# small.net
KiCad netlist of a schematic drawn in EAGLE
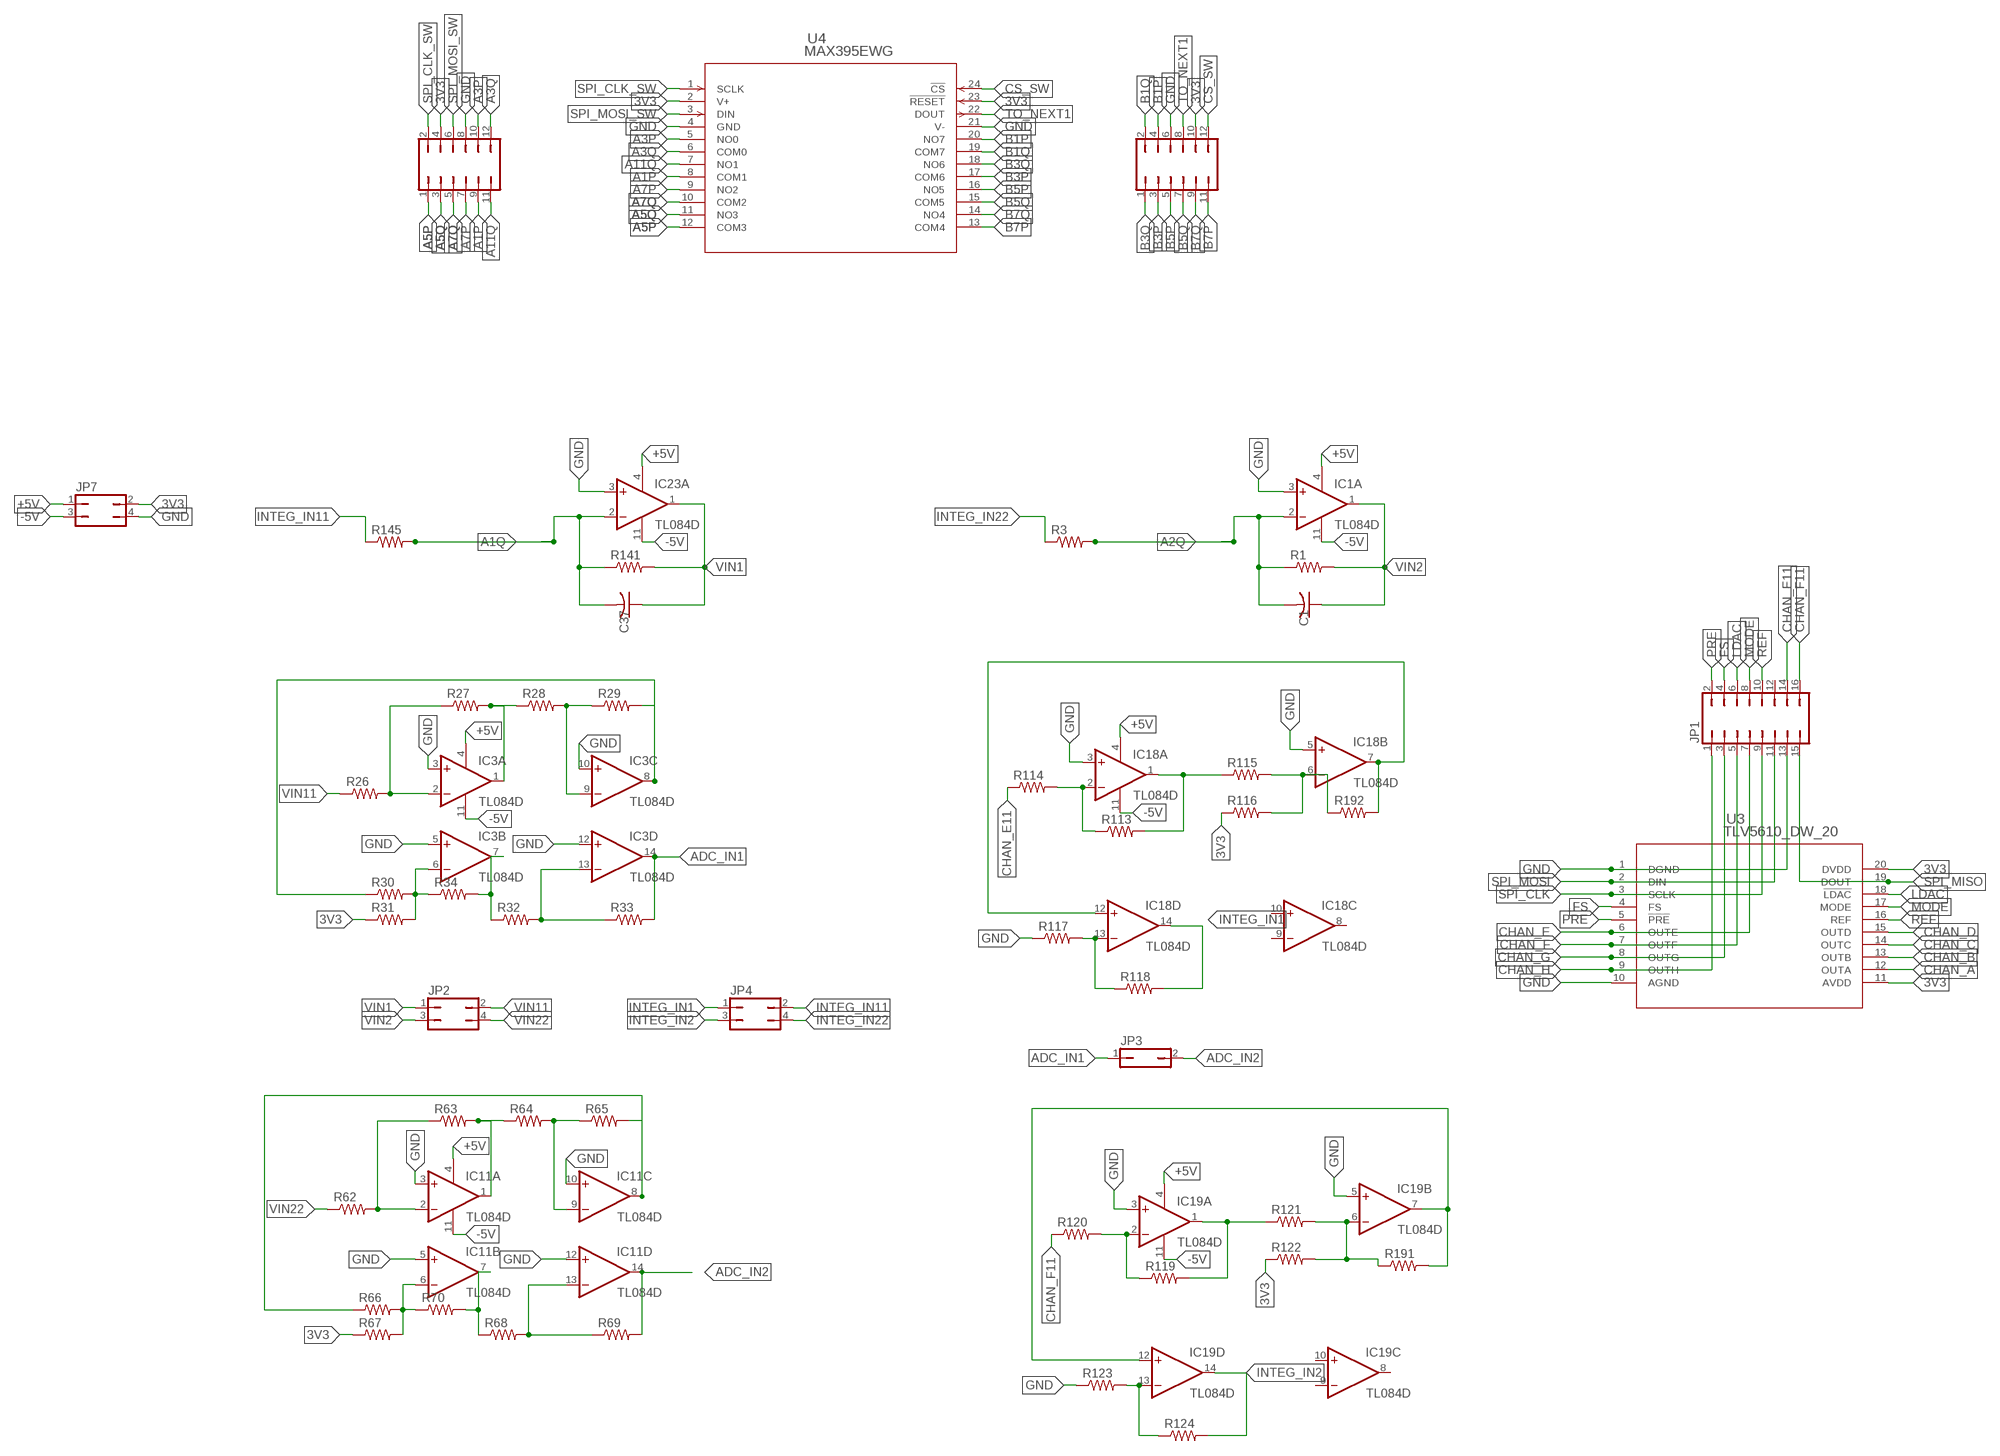
[diagram p0: schematic, sheet 1]

(export (version "E")
  (design (tool "Eeschema 10.0.6"))
  (components
    (comp (ref "C1")
      (value "C-USC1206")
      (footprint "eagle-import:C1206")
      (libsource (lib "eagle-import") (part "C-USC1206"))
    )
    (comp (ref "C37")
      (value "C-USC1206")
      (footprint "eagle-import:C1206")
      (libsource (lib "eagle-import") (part "C-USC1206"))
    )
    (comp (ref "IC1")
      (value "TL084D")
      (footprint "eagle-import:SO14")
      (libsource (lib "eagle-import") (part "TL084D"))
    )
    (comp (ref "IC3")
      (value "TL084D")
      (footprint "eagle-import:SO14")
      (libsource (lib "eagle-import") (part "TL084D"))
    )
    (comp (ref "IC11")
      (value "TL084D")
      (footprint "eagle-import:SO14")
      (libsource (lib "eagle-import") (part "TL084D"))
    )
    (comp (ref "IC18")
      (value "TL084D")
      (footprint "eagle-import:SO14")
      (libsource (lib "eagle-import") (part "TL084D"))
    )
    (comp (ref "IC19")
      (value "TL084D")
      (footprint "eagle-import:SO14")
      (libsource (lib "eagle-import") (part "TL084D"))
    )
    (comp (ref "IC23")
      (value "TL084D")
      (footprint "eagle-import:SO14")
      (libsource (lib "eagle-import") (part "TL084D"))
    )
    (comp (ref "JP1")
      (value "JP8Q")
      (footprint "eagle-import:JP8Q")
      (libsource (lib "eagle-import") (part "JP8Q"))
    )
    (comp (ref "JP2")
      (value "JP2Q")
      (footprint "eagle-import:JP2Q")
      (libsource (lib "eagle-import") (part "JP2Q"))
    )
    (comp (ref "JP3")
      (value "JP1Q")
      (footprint "eagle-import:JP1")
      (libsource (lib "eagle-import") (part "JP1Q"))
    )
    (comp (ref "JP4")
      (value "JP2Q")
      (footprint "eagle-import:JP2Q")
      (libsource (lib "eagle-import") (part "JP2Q"))
    )
    (comp (ref "JP5")
      (value "JP6Q")
      (footprint "eagle-import:JP6Q")
      (libsource (lib "eagle-import") (part "JP6Q"))
    )
    (comp (ref "JP6")
      (value "JP6Q")
      (footprint "eagle-import:JP6Q")
      (libsource (lib "eagle-import") (part "JP6Q"))
    )
    (comp (ref "JP7")
      (value "JP2Q")
      (footprint "eagle-import:JP2Q")
      (libsource (lib "eagle-import") (part "JP2Q"))
    )
    (comp (ref "R1")
      (value "R-US_R1206")
      (footprint "eagle-import:R1206")
      (libsource (lib "eagle-import") (part "R-US_R1206"))
    )
    (comp (ref "R3")
      (value "R-US_R1206")
      (footprint "eagle-import:R1206")
      (libsource (lib "eagle-import") (part "R-US_R1206"))
    )
    (comp (ref "R26")
      (value "R-US_R1206")
      (footprint "eagle-import:R1206")
      (libsource (lib "eagle-import") (part "R-US_R1206"))
    )
    (comp (ref "R27")
      (value "R-US_R1206")
      (footprint "eagle-import:R1206")
      (libsource (lib "eagle-import") (part "R-US_R1206"))
    )
    (comp (ref "R28")
      (value "R-US_R1206")
      (footprint "eagle-import:R1206")
      (libsource (lib "eagle-import") (part "R-US_R1206"))
    )
    (comp (ref "R29")
      (value "R-US_R1206")
      (footprint "eagle-import:R1206")
      (libsource (lib "eagle-import") (part "R-US_R1206"))
    )
    (comp (ref "R30")
      (value "R-US_R1206")
      (footprint "eagle-import:R1206")
      (libsource (lib "eagle-import") (part "R-US_R1206"))
    )
    (comp (ref "R31")
      (value "R-US_R1206")
      (footprint "eagle-import:R1206")
      (libsource (lib "eagle-import") (part "R-US_R1206"))
    )
    (comp (ref "R32")
      (value "R-US_R1206")
      (footprint "eagle-import:R1206")
      (libsource (lib "eagle-import") (part "R-US_R1206"))
    )
    (comp (ref "R33")
      (value "R-US_R1206")
      (footprint "eagle-import:R1206")
      (libsource (lib "eagle-import") (part "R-US_R1206"))
    )
    (comp (ref "R34")
      (value "R-US_R1206")
      (footprint "eagle-import:R1206")
      (libsource (lib "eagle-import") (part "R-US_R1206"))
    )
    (comp (ref "R62")
      (value "R-US_R1206")
      (footprint "eagle-import:R1206")
      (libsource (lib "eagle-import") (part "R-US_R1206"))
    )
    (comp (ref "R63")
      (value "R-US_R1206")
      (footprint "eagle-import:R1206")
      (libsource (lib "eagle-import") (part "R-US_R1206"))
    )
    (comp (ref "R64")
      (value "R-US_R1206")
      (footprint "eagle-import:R1206")
      (libsource (lib "eagle-import") (part "R-US_R1206"))
    )
    (comp (ref "R65")
      (value "R-US_R1206")
      (footprint "eagle-import:R1206")
      (libsource (lib "eagle-import") (part "R-US_R1206"))
    )
    (comp (ref "R66")
      (value "R-US_R1206")
      (footprint "eagle-import:R1206")
      (libsource (lib "eagle-import") (part "R-US_R1206"))
    )
    (comp (ref "R67")
      (value "R-US_R1206")
      (footprint "eagle-import:R1206")
      (libsource (lib "eagle-import") (part "R-US_R1206"))
    )
    (comp (ref "R68")
      (value "R-US_R1206")
      (footprint "eagle-import:R1206")
      (libsource (lib "eagle-import") (part "R-US_R1206"))
    )
    (comp (ref "R69")
      (value "R-US_R1206")
      (footprint "eagle-import:R1206")
      (libsource (lib "eagle-import") (part "R-US_R1206"))
    )
    (comp (ref "R70")
      (value "R-US_R1206")
      (footprint "eagle-import:R1206")
      (libsource (lib "eagle-import") (part "R-US_R1206"))
    )
    (comp (ref "R113")
      (value "R-US_R1206")
      (footprint "eagle-import:R1206")
      (libsource (lib "eagle-import") (part "R-US_R1206"))
    )
    (comp (ref "R114")
      (value "R-US_R1206")
      (footprint "eagle-import:R1206")
      (libsource (lib "eagle-import") (part "R-US_R1206"))
    )
    (comp (ref "R115")
      (value "R-US_R1206")
      (footprint "eagle-import:R1206")
      (libsource (lib "eagle-import") (part "R-US_R1206"))
    )
    (comp (ref "R116")
      (value "R-US_R1206")
      (footprint "eagle-import:R1206")
      (libsource (lib "eagle-import") (part "R-US_R1206"))
    )
    (comp (ref "R117")
      (value "R-US_R1206")
      (footprint "eagle-import:R1206")
      (libsource (lib "eagle-import") (part "R-US_R1206"))
    )
    (comp (ref "R118")
      (value "R-US_R1206")
      (footprint "eagle-import:R1206")
      (libsource (lib "eagle-import") (part "R-US_R1206"))
    )
    (comp (ref "R119")
      (value "R-US_R1206")
      (footprint "eagle-import:R1206")
      (libsource (lib "eagle-import") (part "R-US_R1206"))
    )
    (comp (ref "R120")
      (value "R-US_R1206")
      (footprint "eagle-import:R1206")
      (libsource (lib "eagle-import") (part "R-US_R1206"))
    )
    (comp (ref "R121")
      (value "R-US_R1206")
      (footprint "eagle-import:R1206")
      (libsource (lib "eagle-import") (part "R-US_R1206"))
    )
    (comp (ref "R122")
      (value "R-US_R1206")
      (footprint "eagle-import:R1206")
      (libsource (lib "eagle-import") (part "R-US_R1206"))
    )
    (comp (ref "R123")
      (value "R-US_R1206")
      (footprint "eagle-import:R1206")
      (libsource (lib "eagle-import") (part "R-US_R1206"))
    )
    (comp (ref "R124")
      (value "R-US_R1206")
      (footprint "eagle-import:R1206")
      (libsource (lib "eagle-import") (part "R-US_R1206"))
    )
    (comp (ref "R141")
      (value "R-US_R1206")
      (footprint "eagle-import:R1206")
      (libsource (lib "eagle-import") (part "R-US_R1206"))
    )
    (comp (ref "R145")
      (value "R-US_R1206")
      (footprint "eagle-import:R1206")
      (libsource (lib "eagle-import") (part "R-US_R1206"))
    )
    (comp (ref "R191")
      (value "R-US_R1206")
      (footprint "eagle-import:R1206")
      (libsource (lib "eagle-import") (part "R-US_R1206"))
    )
    (comp (ref "R192")
      (value "R-US_R1206")
      (footprint "eagle-import:R1206")
      (libsource (lib "eagle-import") (part "R-US_R1206"))
    )
    (comp (ref "U3")
      (value "TLV5610_DW_20")
      (footprint "eagle-import:DW20")
      (libsource (lib "eagle-import") (part "TLV5610_DW_20"))
    )
    (comp (ref "U4")
      (value "MAX395EWG")
      (footprint "eagle-import:21-0042B_24")
      (fields (field (name "MANUFACTURER_PART_NUMBER") "max395ewg"))
      (libsource (lib "eagle-import") (part "MAX395EWG"))
    )
  )
  (nets
    (net (code "1") (name "+5V") (class "Default")
      (node (ref "IC1") (pin "4") (pinfunction "V+_4") (pintype "power_in"))
      (node (ref "IC11") (pin "4") (pinfunction "V+_4") (pintype "power_in"))
      (node (ref "IC18") (pin "4") (pinfunction "V+_4") (pintype "power_in"))
      (node (ref "IC19") (pin "4") (pinfunction "V+_4") (pintype "power_in"))
      (node (ref "IC23") (pin "4") (pinfunction "V+_4") (pintype "power_in"))
      (node (ref "IC3") (pin "4") (pinfunction "V+_4") (pintype "power_in"))
      (node (ref "JP7") (pin "1") (pinfunction "1_1") (pintype "passive"))
    )
    (net (code "2") (name "-5V") (class "Default")
      (node (ref "IC1") (pin "11") (pinfunction "V-_11") (pintype "power_in"))
      (node (ref "IC11") (pin "11") (pinfunction "V-_11") (pintype "power_in"))
      (node (ref "IC18") (pin "11") (pinfunction "V-_11") (pintype "power_in"))
      (node (ref "IC19") (pin "11") (pinfunction "V-_11") (pintype "power_in"))
      (node (ref "IC23") (pin "11") (pinfunction "V-_11") (pintype "power_in"))
      (node (ref "IC3") (pin "11") (pinfunction "V-_11") (pintype "power_in"))
      (node (ref "JP7") (pin "3") (pinfunction "3_3") (pintype "passive"))
    )
    (net (code "3") (name "3V3") (class "Default")
      (node (ref "JP5") (pin "4") (pinfunction "4_4") (pintype "passive"))
      (node (ref "JP6") (pin "10") (pinfunction "10_10") (pintype "passive"))
      (node (ref "JP7") (pin "2") (pinfunction "2_2") (pintype "passive"))
      (node (ref "R116") (pin "1") (pinfunction "1_1") (pintype "passive"))
      (node (ref "R122") (pin "1") (pinfunction "1_1") (pintype "passive"))
      (node (ref "R31") (pin "1") (pinfunction "1_1") (pintype "passive"))
      (node (ref "R67") (pin "1") (pinfunction "1_1") (pintype "passive"))
      (node (ref "U3") (pin "11") (pinfunction "AVDD_11") (pintype "power_in"))
      (node (ref "U3") (pin "20") (pinfunction "DVDD_20") (pintype "power_in"))
      (node (ref "U4") (pin "2") (pinfunction "V+_2") (pintype "power_in"))
      (node (ref "U4") (pin "23") (pinfunction "~{RESET}_23") (pintype "input"))
    )
    (net (code "4") (name "A1P") (class "Default")
      (node (ref "JP5") (pin "9") (pinfunction "9_9") (pintype "passive"))
      (node (ref "U4") (pin "8") (pinfunction "COM1_8") (pintype "passive"))
    )
    (net (code "5") (name "A1Q") (class "Default")
      (node (ref "C37") (pin "2") (pinfunction "2_2") (pintype "passive"))
      (node (ref "IC23") (pin "2") (pinfunction "-IN_2") (pintype "input"))
      (node (ref "R141") (pin "1") (pinfunction "1_1") (pintype "passive"))
      (node (ref "R145") (pin "2") (pinfunction "2_2") (pintype "passive"))
    )
    (net (code "6") (name "A2Q") (class "Default")
      (node (ref "C1") (pin "2") (pinfunction "2_2") (pintype "passive"))
      (node (ref "IC1") (pin "2") (pinfunction "-IN_2") (pintype "input"))
      (node (ref "R1") (pin "1") (pinfunction "1_1") (pintype "passive"))
      (node (ref "R3") (pin "2") (pinfunction "2_2") (pintype "passive"))
    )
    (net (code "7") (name "A3P") (class "Default")
      (node (ref "JP5") (pin "10") (pinfunction "10_10") (pintype "passive"))
      (node (ref "U4") (pin "5") (pinfunction "NO0_5") (pintype "passive"))
    )
    (net (code "8") (name "A3Q") (class "Default")
      (node (ref "JP5") (pin "12") (pinfunction "12_12") (pintype "passive"))
      (node (ref "U4") (pin "6") (pinfunction "COM0_6") (pintype "passive"))
    )
    (net (code "9") (name "A5P") (class "Default")
      (node (ref "JP5") (pin "1") (pinfunction "1_1") (pintype "passive"))
      (node (ref "U4") (pin "12") (pinfunction "COM3_12") (pintype "passive"))
    )
    (net (code "10") (name "A5Q") (class "Default")
      (node (ref "JP5") (pin "3") (pinfunction "3_3") (pintype "passive"))
      (node (ref "U4") (pin "11") (pinfunction "NO3_11") (pintype "passive"))
    )
    (net (code "11") (name "A7P") (class "Default")
      (node (ref "JP5") (pin "7") (pinfunction "7_7") (pintype "passive"))
      (node (ref "U4") (pin "9") (pinfunction "NO2_9") (pintype "passive"))
    )
    (net (code "12") (name "A7Q") (class "Default")
      (node (ref "JP5") (pin "5") (pinfunction "5_5") (pintype "passive"))
      (node (ref "U4") (pin "10") (pinfunction "COM2_10") (pintype "passive"))
    )
    (net (code "13") (name "A11Q") (class "Default")
      (node (ref "JP5") (pin "11") (pinfunction "11_11") (pintype "passive"))
      (node (ref "U4") (pin "7") (pinfunction "NO1_7") (pintype "passive"))
    )
    (net (code "14") (name "ADC_IN1") (class "Default")
      (node (ref "IC3") (pin "14") (pinfunction "OUT_14") (pintype "output"))
      (node (ref "JP3") (pin "1") (pinfunction "1_1") (pintype "passive"))
      (node (ref "R33") (pin "2") (pinfunction "2_2") (pintype "passive"))
    )
    (net (code "15") (name "ADC_IN2") (class "Default")
      (node (ref "IC11") (pin "14") (pinfunction "OUT_14") (pintype "output"))
      (node (ref "JP3") (pin "2") (pinfunction "2_2") (pintype "passive"))
      (node (ref "R69") (pin "2") (pinfunction "2_2") (pintype "passive"))
    )
    (net (code "16") (name "B1P") (class "Default")
      (node (ref "JP6") (pin "4") (pinfunction "4_4") (pintype "passive"))
      (node (ref "U4") (pin "20") (pinfunction "NO7_20") (pintype "passive"))
    )
    (net (code "17") (name "B1Q") (class "Default")
      (node (ref "JP6") (pin "2") (pinfunction "2_2") (pintype "passive"))
      (node (ref "U4") (pin "19") (pinfunction "COM7_19") (pintype "passive"))
    )
    (net (code "18") (name "B3P") (class "Default")
      (node (ref "JP6") (pin "3") (pinfunction "3_3") (pintype "passive"))
      (node (ref "U4") (pin "17") (pinfunction "COM6_17") (pintype "passive"))
    )
    (net (code "19") (name "B3Q") (class "Default")
      (node (ref "JP6") (pin "1") (pinfunction "1_1") (pintype "passive"))
      (node (ref "U4") (pin "18") (pinfunction "NO6_18") (pintype "passive"))
    )
    (net (code "20") (name "B5P") (class "Default")
      (node (ref "JP6") (pin "5") (pinfunction "5_5") (pintype "passive"))
      (node (ref "U4") (pin "16") (pinfunction "NO5_16") (pintype "passive"))
    )
    (net (code "21") (name "B5Q") (class "Default")
      (node (ref "JP6") (pin "7") (pinfunction "7_7") (pintype "passive"))
      (node (ref "U4") (pin "15") (pinfunction "COM5_15") (pintype "passive"))
    )
    (net (code "22") (name "B7P") (class "Default")
      (node (ref "JP6") (pin "11") (pinfunction "11_11") (pintype "passive"))
      (node (ref "U4") (pin "13") (pinfunction "COM4_13") (pintype "passive"))
    )
    (net (code "23") (name "B7Q") (class "Default")
      (node (ref "JP6") (pin "9") (pinfunction "9_9") (pintype "passive"))
      (node (ref "U4") (pin "14") (pinfunction "NO4_14") (pintype "passive"))
    )
    (net (code "24") (name "CHAN_A") (class "Default")
      (node (ref "U3") (pin "12") (pinfunction "OUTA_12") (pintype "output"))
    )
    (net (code "25") (name "CHAN_B") (class "Default")
      (node (ref "U3") (pin "13") (pinfunction "OUTB_13") (pintype "output"))
    )
    (net (code "26") (name "CHAN_C") (class "Default")
      (node (ref "U3") (pin "14") (pinfunction "OUTC_14") (pintype "output"))
    )
    (net (code "27") (name "CHAN_D") (class "Default")
      (node (ref "U3") (pin "15") (pinfunction "OUTD_15") (pintype "output"))
    )
    (net (code "28") (name "CHAN_E") (class "Default")
      (node (ref "JP1") (pin "7") (pinfunction "7_7") (pintype "passive"))
      (node (ref "U3") (pin "6") (pinfunction "OUTE_6") (pintype "output"))
    )
    (net (code "29") (name "CHAN_E11") (class "Default")
      (node (ref "JP1") (pin "14") (pinfunction "14_14") (pintype "passive"))
      (node (ref "R114") (pin "1") (pinfunction "1_1") (pintype "passive"))
    )
    (net (code "30") (name "CHAN_F") (class "Default")
      (node (ref "JP1") (pin "5") (pinfunction "5_5") (pintype "passive"))
      (node (ref "U3") (pin "7") (pinfunction "OUTF_7") (pintype "output"))
    )
    (net (code "31") (name "CHAN_F11") (class "Default")
      (node (ref "JP1") (pin "16") (pinfunction "16_16") (pintype "passive"))
      (node (ref "R120") (pin "1") (pinfunction "1_1") (pintype "passive"))
    )
    (net (code "32") (name "CHAN_G") (class "Default")
      (node (ref "JP1") (pin "3") (pinfunction "3_3") (pintype "passive"))
      (node (ref "U3") (pin "8") (pinfunction "OUTG_8") (pintype "output"))
    )
    (net (code "33") (name "CHAN_H") (class "Default")
      (node (ref "JP1") (pin "1") (pinfunction "1_1") (pintype "passive"))
      (node (ref "U3") (pin "9") (pinfunction "OUTH_9") (pintype "output"))
    )
    (net (code "34") (name "CS_SW") (class "Default")
      (node (ref "JP6") (pin "12") (pinfunction "12_12") (pintype "passive"))
      (node (ref "U4") (pin "24") (pinfunction "~{CS}_24") (pintype "input"))
    )
    (net (code "35") (name "FS") (class "Default")
      (node (ref "JP1") (pin "4") (pinfunction "4_4") (pintype "passive"))
      (node (ref "U3") (pin "4") (pinfunction "FS_4") (pintype "input"))
    )
    (net (code "36") (name "GND") (class "Default")
      (node (ref "IC1") (pin "3") (pinfunction "+IN_3") (pintype "input"))
      (node (ref "IC11") (pin "10") (pinfunction "+IN_10") (pintype "input"))
      (node (ref "IC11") (pin "12") (pinfunction "+IN_12") (pintype "input"))
      (node (ref "IC11") (pin "3") (pinfunction "+IN_3") (pintype "input"))
      (node (ref "IC11") (pin "5") (pinfunction "+IN_5") (pintype "input"))
      (node (ref "IC18") (pin "3") (pinfunction "+IN_3") (pintype "input"))
      (node (ref "IC18") (pin "5") (pinfunction "+IN_5") (pintype "input"))
      (node (ref "IC19") (pin "3") (pinfunction "+IN_3") (pintype "input"))
      (node (ref "IC19") (pin "5") (pinfunction "+IN_5") (pintype "input"))
      (node (ref "IC23") (pin "3") (pinfunction "+IN_3") (pintype "input"))
      (node (ref "IC3") (pin "10") (pinfunction "+IN_10") (pintype "input"))
      (node (ref "IC3") (pin "12") (pinfunction "+IN_12") (pintype "input"))
      (node (ref "IC3") (pin "3") (pinfunction "+IN_3") (pintype "input"))
      (node (ref "IC3") (pin "5") (pinfunction "+IN_5") (pintype "input"))
      (node (ref "JP1") (pin "13") (pinfunction "13_13") (pintype "passive"))
      (node (ref "JP5") (pin "8") (pinfunction "8_8") (pintype "passive"))
      (node (ref "JP6") (pin "6") (pinfunction "6_6") (pintype "passive"))
      (node (ref "JP7") (pin "4") (pinfunction "4_4") (pintype "passive"))
      (node (ref "R117") (pin "1") (pinfunction "1_1") (pintype "passive"))
      (node (ref "R123") (pin "1") (pinfunction "1_1") (pintype "passive"))
      (node (ref "U3") (pin "1") (pinfunction "DGND_1") (pintype "power_in"))
      (node (ref "U3") (pin "10") (pinfunction "AGND_10") (pintype "power_in"))
      (node (ref "U4") (pin "21") (pinfunction "V-_21") (pintype "power_in"))
      (node (ref "U4") (pin "4") (pinfunction "GND_4") (pintype "power_in"))
    )
    (net (code "37") (name "INTEG_IN1") (class "Default")
      (node (ref "IC18") (pin "14") (pinfunction "OUT_14") (pintype "output"))
      (node (ref "JP4") (pin "1") (pinfunction "1_1") (pintype "passive"))
      (node (ref "R118") (pin "2") (pinfunction "2_2") (pintype "passive"))
    )
    (net (code "38") (name "INTEG_IN2") (class "Default")
      (node (ref "IC19") (pin "14") (pinfunction "OUT_14") (pintype "output"))
      (node (ref "JP4") (pin "3") (pinfunction "3_3") (pintype "passive"))
      (node (ref "R124") (pin "2") (pinfunction "2_2") (pintype "passive"))
    )
    (net (code "39") (name "INTEG_IN11") (class "Default")
      (node (ref "JP4") (pin "2") (pinfunction "2_2") (pintype "passive"))
      (node (ref "R145") (pin "1") (pinfunction "1_1") (pintype "passive"))
    )
    (net (code "40") (name "INTEG_IN22") (class "Default")
      (node (ref "JP4") (pin "4") (pinfunction "4_4") (pintype "passive"))
      (node (ref "R3") (pin "1") (pinfunction "1_1") (pintype "passive"))
    )
    (net (code "41") (name "LDAC") (class "Default")
      (node (ref "JP1") (pin "6") (pinfunction "6_6") (pintype "passive"))
      (node (ref "U3") (pin "18") (pinfunction "~{LDAC}_18") (pintype "input"))
    )
    (net (code "42") (name "MODE") (class "Default")
      (node (ref "JP1") (pin "8") (pinfunction "8_8") (pintype "passive"))
      (node (ref "U3") (pin "17") (pinfunction "MODE_17") (pintype "input"))
    )
    (net (code "43") (name "Net-(IC3A--IN)") (class "Default")
      (node (ref "IC3") (pin "2") (pinfunction "-IN_2") (pintype "input"))
      (node (ref "R26") (pin "2") (pinfunction "2_2") (pintype "passive"))
      (node (ref "R27") (pin "1") (pinfunction "1_1") (pintype "passive"))
    )
    (net (code "44") (name "Net-(IC3A-OUT)") (class "Default")
      (node (ref "IC3") (pin "1") (pinfunction "OUT_1") (pintype "output"))
      (node (ref "R27") (pin "2") (pinfunction "2_2") (pintype "passive"))
      (node (ref "R28") (pin "1") (pinfunction "1_1") (pintype "passive"))
    )
    (net (code "45") (name "Net-(IC3B--IN)") (class "Default")
      (node (ref "IC3") (pin "6") (pinfunction "-IN_6") (pintype "input"))
      (node (ref "R30") (pin "2") (pinfunction "2_2") (pintype "passive"))
      (node (ref "R31") (pin "2") (pinfunction "2_2") (pintype "passive"))
      (node (ref "R34") (pin "1") (pinfunction "1_1") (pintype "passive"))
    )
    (net (code "46") (name "Net-(IC3B-OUT)") (class "Default")
      (node (ref "IC3") (pin "7") (pinfunction "OUT_7") (pintype "output"))
      (node (ref "R32") (pin "1") (pinfunction "1_1") (pintype "passive"))
      (node (ref "R34") (pin "2") (pinfunction "2_2") (pintype "passive"))
    )
    (net (code "47") (name "Net-(IC3C--IN)") (class "Default")
      (node (ref "IC3") (pin "9") (pinfunction "-IN_9") (pintype "input"))
      (node (ref "R28") (pin "2") (pinfunction "2_2") (pintype "passive"))
      (node (ref "R29") (pin "1") (pinfunction "1_1") (pintype "passive"))
    )
    (net (code "48") (name "Net-(IC3C-OUT)") (class "Default")
      (node (ref "IC3") (pin "8") (pinfunction "OUT_8") (pintype "output"))
      (node (ref "R29") (pin "2") (pinfunction "2_2") (pintype "passive"))
      (node (ref "R30") (pin "1") (pinfunction "1_1") (pintype "passive"))
    )
    (net (code "49") (name "Net-(IC3D--IN)") (class "Default")
      (node (ref "IC3") (pin "13") (pinfunction "-IN_13") (pintype "input"))
      (node (ref "R32") (pin "2") (pinfunction "2_2") (pintype "passive"))
      (node (ref "R33") (pin "1") (pinfunction "1_1") (pintype "passive"))
    )
    (net (code "50") (name "Net-(IC11A--IN)") (class "Default")
      (node (ref "IC11") (pin "2") (pinfunction "-IN_2") (pintype "input"))
      (node (ref "R62") (pin "2") (pinfunction "2_2") (pintype "passive"))
      (node (ref "R63") (pin "1") (pinfunction "1_1") (pintype "passive"))
    )
    (net (code "51") (name "Net-(IC11A-OUT)") (class "Default")
      (node (ref "IC11") (pin "1") (pinfunction "OUT_1") (pintype "output"))
      (node (ref "R63") (pin "2") (pinfunction "2_2") (pintype "passive"))
      (node (ref "R64") (pin "1") (pinfunction "1_1") (pintype "passive"))
    )
    (net (code "52") (name "Net-(IC11B--IN)") (class "Default")
      (node (ref "IC11") (pin "6") (pinfunction "-IN_6") (pintype "input"))
      (node (ref "R66") (pin "2") (pinfunction "2_2") (pintype "passive"))
      (node (ref "R67") (pin "2") (pinfunction "2_2") (pintype "passive"))
      (node (ref "R70") (pin "1") (pinfunction "1_1") (pintype "passive"))
    )
    (net (code "53") (name "Net-(IC11B-OUT)") (class "Default")
      (node (ref "IC11") (pin "7") (pinfunction "OUT_7") (pintype "output"))
      (node (ref "R68") (pin "1") (pinfunction "1_1") (pintype "passive"))
      (node (ref "R70") (pin "2") (pinfunction "2_2") (pintype "passive"))
    )
    (net (code "54") (name "Net-(IC11C--IN)") (class "Default")
      (node (ref "IC11") (pin "9") (pinfunction "-IN_9") (pintype "input"))
      (node (ref "R64") (pin "2") (pinfunction "2_2") (pintype "passive"))
      (node (ref "R65") (pin "1") (pinfunction "1_1") (pintype "passive"))
    )
    (net (code "55") (name "Net-(IC11C-OUT)") (class "Default")
      (node (ref "IC11") (pin "8") (pinfunction "OUT_8") (pintype "output"))
      (node (ref "R65") (pin "2") (pinfunction "2_2") (pintype "passive"))
      (node (ref "R66") (pin "1") (pinfunction "1_1") (pintype "passive"))
    )
    (net (code "56") (name "Net-(IC11D--IN)") (class "Default")
      (node (ref "IC11") (pin "13") (pinfunction "-IN_13") (pintype "input"))
      (node (ref "R68") (pin "2") (pinfunction "2_2") (pintype "passive"))
      (node (ref "R69") (pin "1") (pinfunction "1_1") (pintype "passive"))
    )
    (net (code "57") (name "Net-(IC18A--IN)") (class "Default")
      (node (ref "IC18") (pin "2") (pinfunction "-IN_2") (pintype "input"))
      (node (ref "R113") (pin "1") (pinfunction "1_1") (pintype "passive"))
      (node (ref "R114") (pin "2") (pinfunction "2_2") (pintype "passive"))
    )
    (net (code "58") (name "Net-(IC18A-OUT)") (class "Default")
      (node (ref "IC18") (pin "1") (pinfunction "OUT_1") (pintype "output"))
      (node (ref "R113") (pin "2") (pinfunction "2_2") (pintype "passive"))
      (node (ref "R115") (pin "1") (pinfunction "1_1") (pintype "passive"))
    )
    (net (code "59") (name "Net-(IC18B--IN)") (class "Default")
      (node (ref "IC18") (pin "6") (pinfunction "-IN_6") (pintype "input"))
      (node (ref "R115") (pin "2") (pinfunction "2_2") (pintype "passive"))
      (node (ref "R116") (pin "2") (pinfunction "2_2") (pintype "passive"))
      (node (ref "R192") (pin "1") (pinfunction "1_1") (pintype "passive"))
    )
    (net (code "60") (name "Net-(IC18B-OUT)") (class "Default")
      (node (ref "IC18") (pin "12") (pinfunction "+IN_12") (pintype "input"))
      (node (ref "IC18") (pin "7") (pinfunction "OUT_7") (pintype "output"))
      (node (ref "R192") (pin "2") (pinfunction "2_2") (pintype "passive"))
    )
    (net (code "61") (name "Net-(IC18D--IN)") (class "Default")
      (node (ref "IC18") (pin "13") (pinfunction "-IN_13") (pintype "input"))
      (node (ref "R117") (pin "2") (pinfunction "2_2") (pintype "passive"))
      (node (ref "R118") (pin "1") (pinfunction "1_1") (pintype "passive"))
    )
    (net (code "62") (name "Net-(IC19A--IN)") (class "Default")
      (node (ref "IC19") (pin "2") (pinfunction "-IN_2") (pintype "input"))
      (node (ref "R119") (pin "1") (pinfunction "1_1") (pintype "passive"))
      (node (ref "R120") (pin "2") (pinfunction "2_2") (pintype "passive"))
    )
    (net (code "63") (name "Net-(IC19A-OUT)") (class "Default")
      (node (ref "IC19") (pin "1") (pinfunction "OUT_1") (pintype "output"))
      (node (ref "R119") (pin "2") (pinfunction "2_2") (pintype "passive"))
      (node (ref "R121") (pin "1") (pinfunction "1_1") (pintype "passive"))
    )
    (net (code "64") (name "Net-(IC19B--IN)") (class "Default")
      (node (ref "IC19") (pin "6") (pinfunction "-IN_6") (pintype "input"))
      (node (ref "R121") (pin "2") (pinfunction "2_2") (pintype "passive"))
      (node (ref "R122") (pin "2") (pinfunction "2_2") (pintype "passive"))
      (node (ref "R191") (pin "1") (pinfunction "1_1") (pintype "passive"))
    )
    (net (code "65") (name "Net-(IC19B-OUT)") (class "Default")
      (node (ref "IC19") (pin "12") (pinfunction "+IN_12") (pintype "input"))
      (node (ref "IC19") (pin "7") (pinfunction "OUT_7") (pintype "output"))
      (node (ref "R191") (pin "2") (pinfunction "2_2") (pintype "passive"))
    )
    (net (code "66") (name "Net-(IC19D--IN)") (class "Default")
      (node (ref "IC19") (pin "13") (pinfunction "-IN_13") (pintype "input"))
      (node (ref "R123") (pin "2") (pinfunction "2_2") (pintype "passive"))
      (node (ref "R124") (pin "1") (pinfunction "1_1") (pintype "passive"))
    )
    (net (code "67") (name "PRE") (class "Default")
      (node (ref "JP1") (pin "2") (pinfunction "2_2") (pintype "passive"))
      (node (ref "U3") (pin "5") (pinfunction "~{PRE}_5") (pintype "input"))
    )
    (net (code "68") (name "REF") (class "Default")
      (node (ref "JP1") (pin "10") (pinfunction "10_10") (pintype "passive"))
      (node (ref "U3") (pin "16") (pinfunction "REF_16") (pintype "input"))
    )
    (net (code "69") (name "SPI_CLK") (class "Default")
      (node (ref "JP1") (pin "9") (pinfunction "9_9") (pintype "passive"))
      (node (ref "U3") (pin "3") (pinfunction "SCLK_3") (pintype "input"))
    )
    (net (code "70") (name "SPI_CLK_SW") (class "Default")
      (node (ref "JP5") (pin "2") (pinfunction "2_2") (pintype "passive"))
      (node (ref "U4") (pin "1") (pinfunction "SCLK_1") (pintype "input"))
    )
    (net (code "71") (name "SPI_MISO") (class "Default")
      (node (ref "JP1") (pin "15") (pinfunction "15_15") (pintype "passive"))
      (node (ref "U3") (pin "19") (pinfunction "DOUT_19") (pintype "output"))
    )
    (net (code "72") (name "SPI_MOSI") (class "Default")
      (node (ref "JP1") (pin "11") (pinfunction "11_11") (pintype "passive"))
      (node (ref "U3") (pin "2") (pinfunction "DIN_2") (pintype "input"))
    )
    (net (code "73") (name "SPI_MOSI_SW") (class "Default")
      (node (ref "JP5") (pin "6") (pinfunction "6_6") (pintype "passive"))
      (node (ref "U4") (pin "3") (pinfunction "DIN_3") (pintype "input"))
    )
    (net (code "74") (name "TO_NEXT1") (class "Default")
      (node (ref "JP6") (pin "8") (pinfunction "8_8") (pintype "passive"))
      (node (ref "U4") (pin "22") (pinfunction "DOUT_22") (pintype "output"))
    )
    (net (code "75") (name "VIN1") (class "Default")
      (node (ref "C37") (pin "1") (pinfunction "1_1") (pintype "passive"))
      (node (ref "IC23") (pin "1") (pinfunction "OUT_1") (pintype "output"))
      (node (ref "JP2") (pin "1") (pinfunction "1_1") (pintype "passive"))
      (node (ref "R141") (pin "2") (pinfunction "2_2") (pintype "passive"))
    )
    (net (code "76") (name "VIN2") (class "Default")
      (node (ref "C1") (pin "1") (pinfunction "1_1") (pintype "passive"))
      (node (ref "IC1") (pin "1") (pinfunction "OUT_1") (pintype "output"))
      (node (ref "JP2") (pin "3") (pinfunction "3_3") (pintype "passive"))
      (node (ref "R1") (pin "2") (pinfunction "2_2") (pintype "passive"))
    )
    (net (code "77") (name "VIN11") (class "Default")
      (node (ref "JP2") (pin "2") (pinfunction "2_2") (pintype "passive"))
      (node (ref "R26") (pin "1") (pinfunction "1_1") (pintype "passive"))
    )
    (net (code "78") (name "VIN22") (class "Default")
      (node (ref "JP2") (pin "4") (pinfunction "4_4") (pintype "passive"))
      (node (ref "R62") (pin "1") (pinfunction "1_1") (pintype "passive"))
    )
    (net (code "79") (name "unconnected-(IC18C-+IN-Pad10)") (class "Default")
      (node (ref "IC18") (pin "10") (pinfunction "+IN_10") (pintype "input"))
    )
    (net (code "80") (name "unconnected-(IC18C--IN-Pad9)") (class "Default")
      (node (ref "IC18") (pin "9") (pinfunction "-IN_9") (pintype "input"))
    )
    (net (code "81") (name "unconnected-(IC18C-OUT-Pad8)") (class "Default")
      (node (ref "IC18") (pin "8") (pinfunction "OUT_8") (pintype "output"))
    )
    (net (code "82") (name "unconnected-(IC19C-+IN-Pad10)") (class "Default")
      (node (ref "IC19") (pin "10") (pinfunction "+IN_10") (pintype "input"))
    )
    (net (code "83") (name "unconnected-(IC19C--IN-Pad9)") (class "Default")
      (node (ref "IC19") (pin "9") (pinfunction "-IN_9") (pintype "input"))
    )
    (net (code "84") (name "unconnected-(IC19C-OUT-Pad8)") (class "Default")
      (node (ref "IC19") (pin "8") (pinfunction "OUT_8") (pintype "output"))
    )
    (net (code "85") (name "unconnected-(JP1-Pad12)") (class "Default")
      (node (ref "JP1") (pin "12") (pinfunction "12_12") (pintype "passive"))
    )
  )
)
